# Sheet1.net
KiCad netlist of a schematic drawn in Altium Designer
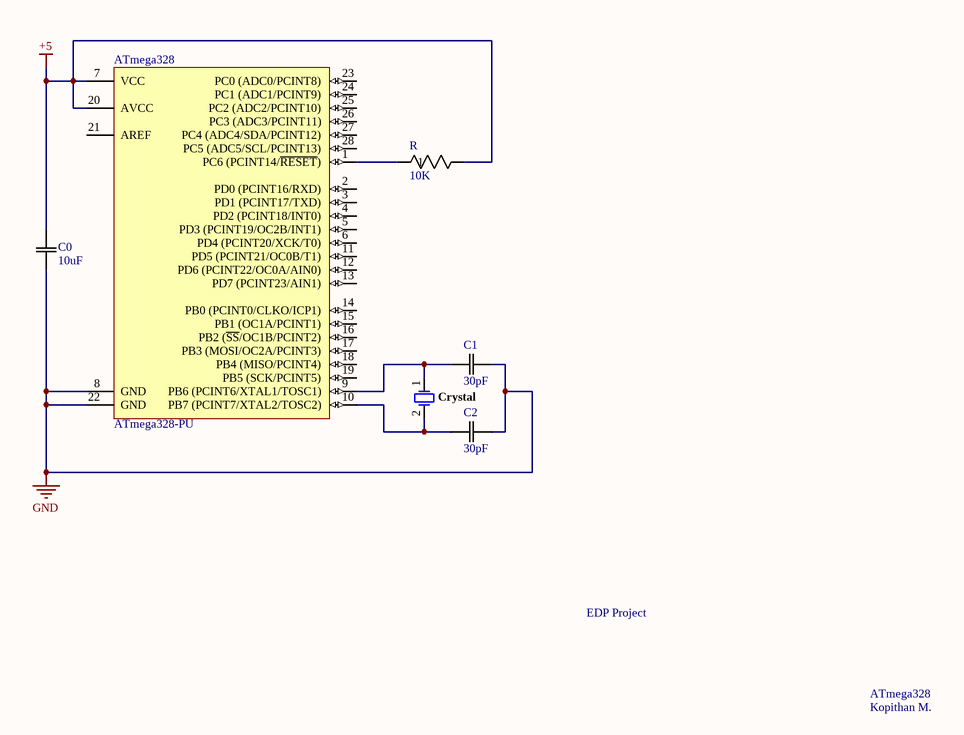
[diagram p0: Sheet1.SchDoc]

(export (version "E")
  (design (tool "Eeschema 10.0.6"))
  (components
    (comp (ref "ATmega328")
      (value "ATmega328-PU")
      (footprint "28P3")
      (libsource (lib "Altium Content Vault") (part "MC-8B-ATM48-IL28"))
    )
    (comp (ref "C0")
      (value "10uF")
      (footprint "CAP_WCAP-PTHR_6P3X8P0_WRE")
      (libsource (lib "870055673001") (part "870055673001"))
    )
    (comp (ref "C1")
      (value "30pF")
      (footprint "CAP_CD15_CND")
      (description "CD15ED300JO3F")
      (libsource (lib "CD15ED300JO3F") (part "CD15ED300JO3F"))
    )
    (comp (ref "C2")
      (value "30pF")
      (footprint "CAP_CD15_CND")
      (description "CD15ED300JO3F")
      (libsource (lib "CD15ED300JO3F") (part "CD15ED300JO3F"))
    )
    (comp (ref "Crystal")
      (value "FOXSLF/160-20")
      (footprint "FOX-FOXSLF160-20")
      (description "Resistance Weld Thru-Hole Crystal, 16 MHz, -20 to 70 degC, 2-Pin THD, RoHS, Bulk")
      (fields (field (name "TOLERANCE") "1%"))
      (libsource (lib "Altium Content Vault") (part "XTAL-1-2-2"))
    )
    (comp (ref "R")
      (value "10K")
      (footprint "RES_TYCO_YR1_TYC")
      (description "30pF")
      (libsource (lib "YR1B10KCC") (part "YR1B10KCC"))
    )
  )
  (nets
    (net (code "1") (name "+5") (class "Default")
      (node (ref "ATmega328") (pin "20") (pinfunction "AVCC_20") (pintype "power_in"))
      (node (ref "ATmega328") (pin "7") (pinfunction "VCC_7") (pintype "power_in"))
      (node (ref "C0") (pin "2") (pinfunction "2_2") (pintype "passive"))
      (node (ref "R") (pin "2") (pinfunction "2_2") (pintype "passive"))
    )
    (net (code "2") (name "GND") (class "Default")
      (node (ref "ATmega328") (pin "22") (pinfunction "GND_22") (pintype "power_in"))
      (node (ref "ATmega328") (pin "8") (pinfunction "GND_8") (pintype "power_in"))
      (node (ref "C0") (pin "1") (pinfunction "1_1") (pintype "passive"))
      (node (ref "C1") (pin "2") (pinfunction "2_2") (pintype "passive"))
      (node (ref "C2") (pin "2") (pinfunction "2_2") (pintype "passive"))
    )
    (net (code "3") (name "Net-(ATmega328-PB6_(PCINT6{slash}XTAL1{slash}TOSC1))") (class "Default")
      (node (ref "ATmega328") (pin "9") (pinfunction "PB6_(PCINT6/XTAL1/TOSC1)_9") (pintype "bidirectional"))
      (node (ref "C1") (pin "1") (pinfunction "1_1") (pintype "passive"))
      (node (ref "Crystal") (pin "1") (pinfunction "1_1") (pintype "passive"))
    )
    (net (code "4") (name "Net-(ATmega328-PB7_(PCINT7{slash}XTAL2{slash}TOSC2))") (class "Default")
      (node (ref "ATmega328") (pin "10") (pinfunction "PB7_(PCINT7/XTAL2/TOSC2)_10") (pintype "bidirectional"))
      (node (ref "C2") (pin "1") (pinfunction "1_1") (pintype "passive"))
      (node (ref "Crystal") (pin "2") (pinfunction "2_2") (pintype "passive"))
    )
    (net (code "5") (name "Net-(ATmega328-PC6_(PCINT14{slash}~{RESET}))") (class "Default")
      (node (ref "ATmega328") (pin "1") (pinfunction "PC6_(PCINT14/~{RESET})_1") (pintype "bidirectional"))
      (node (ref "R") (pin "1") (pinfunction "1_1") (pintype "passive"))
    )
    (net (code "6") (name "unconnected-(ATmega328-AREF-Pad21)") (class "Default")
      (node (ref "ATmega328") (pin "21") (pinfunction "AREF_21") (pintype "power_in"))
    )
    (net (code "7") (name "unconnected-(ATmega328-PB0_(PCINT0{slash}CLKO{slash}ICP1)-Pad14)") (class "Default")
      (node (ref "ATmega328") (pin "14") (pinfunction "PB0_(PCINT0/CLKO/ICP1)_14") (pintype "bidirectional"))
    )
    (net (code "8") (name "unconnected-(ATmega328-PB1_(OC1A{slash}PCINT1)-Pad15)") (class "Default")
      (node (ref "ATmega328") (pin "15") (pinfunction "PB1_(OC1A/PCINT1)_15") (pintype "bidirectional"))
    )
    (net (code "9") (name "unconnected-(ATmega328-PB2_(~{SS}{slash}OC1B{slash}PCINT2)-Pad16)") (class "Default")
      (node (ref "ATmega328") (pin "16") (pinfunction "PB2_(~{SS}/OC1B/PCINT2)_16") (pintype "bidirectional"))
    )
    (net (code "10") (name "unconnected-(ATmega328-PB3_(MOSI{slash}OC2A{slash}PCINT3)-Pad17)") (class "Default")
      (node (ref "ATmega328") (pin "17") (pinfunction "PB3_(MOSI/OC2A/PCINT3)_17") (pintype "bidirectional"))
    )
    (net (code "11") (name "unconnected-(ATmega328-PB4_(MISO{slash}PCINT4)-Pad18)") (class "Default")
      (node (ref "ATmega328") (pin "18") (pinfunction "PB4_(MISO/PCINT4)_18") (pintype "bidirectional"))
    )
    (net (code "12") (name "unconnected-(ATmega328-PB5_(SCK{slash}PCINT5)-Pad19)") (class "Default")
      (node (ref "ATmega328") (pin "19") (pinfunction "PB5_(SCK/PCINT5)_19") (pintype "bidirectional"))
    )
    (net (code "13") (name "unconnected-(ATmega328-PC0_(ADC0{slash}PCINT8)-Pad23)") (class "Default")
      (node (ref "ATmega328") (pin "23") (pinfunction "PC0_(ADC0/PCINT8)_23") (pintype "bidirectional"))
    )
    (net (code "14") (name "unconnected-(ATmega328-PC1_(ADC1{slash}PCINT9)-Pad24)") (class "Default")
      (node (ref "ATmega328") (pin "24") (pinfunction "PC1_(ADC1/PCINT9)_24") (pintype "bidirectional"))
    )
    (net (code "15") (name "unconnected-(ATmega328-PC2_(ADC2{slash}PCINT10)-Pad25)") (class "Default")
      (node (ref "ATmega328") (pin "25") (pinfunction "PC2_(ADC2/PCINT10)_25") (pintype "bidirectional"))
    )
    (net (code "16") (name "unconnected-(ATmega328-PC3_(ADC3{slash}PCINT11)-Pad26)") (class "Default")
      (node (ref "ATmega328") (pin "26") (pinfunction "PC3_(ADC3/PCINT11)_26") (pintype "bidirectional"))
    )
    (net (code "17") (name "unconnected-(ATmega328-PC4_(ADC4{slash}SDA{slash}PCINT12)-Pad27)") (class "Default")
      (node (ref "ATmega328") (pin "27") (pinfunction "PC4_(ADC4/SDA/PCINT12)_27") (pintype "bidirectional"))
    )
    (net (code "18") (name "unconnected-(ATmega328-PC5_(ADC5{slash}SCL{slash}PCINT13)-Pad28)") (class "Default")
      (node (ref "ATmega328") (pin "28") (pinfunction "PC5_(ADC5/SCL/PCINT13)_28") (pintype "bidirectional"))
    )
    (net (code "19") (name "unconnected-(ATmega328-PD0_(PCINT16{slash}RXD)-Pad2)") (class "Default")
      (node (ref "ATmega328") (pin "2") (pinfunction "PD0_(PCINT16/RXD)_2") (pintype "bidirectional"))
    )
    (net (code "20") (name "unconnected-(ATmega328-PD1_(PCINT17{slash}TXD)-Pad3)") (class "Default")
      (node (ref "ATmega328") (pin "3") (pinfunction "PD1_(PCINT17/TXD)_3") (pintype "bidirectional"))
    )
    (net (code "21") (name "unconnected-(ATmega328-PD2_(PCINT18{slash}INT0)-Pad4)") (class "Default")
      (node (ref "ATmega328") (pin "4") (pinfunction "PD2_(PCINT18/INT0)_4") (pintype "bidirectional"))
    )
    (net (code "22") (name "unconnected-(ATmega328-PD3_(PCINT19{slash}OC2B{slash}INT1)-Pad5)") (class "Default")
      (node (ref "ATmega328") (pin "5") (pinfunction "PD3_(PCINT19/OC2B/INT1)_5") (pintype "bidirectional"))
    )
    (net (code "23") (name "unconnected-(ATmega328-PD4_(PCINT20{slash}XCK{slash}T0)-Pad6)") (class "Default")
      (node (ref "ATmega328") (pin "6") (pinfunction "PD4_(PCINT20/XCK/T0)_6") (pintype "bidirectional"))
    )
    (net (code "24") (name "unconnected-(ATmega328-PD5_(PCINT21{slash}OC0B{slash}T1)-Pad11)") (class "Default")
      (node (ref "ATmega328") (pin "11") (pinfunction "PD5_(PCINT21/OC0B/T1)_11") (pintype "bidirectional"))
    )
    (net (code "25") (name "unconnected-(ATmega328-PD6_(PCINT22{slash}OC0A{slash}AIN0)-Pad12)") (class "Default")
      (node (ref "ATmega328") (pin "12") (pinfunction "PD6_(PCINT22/OC0A/AIN0)_12") (pintype "bidirectional"))
    )
    (net (code "26") (name "unconnected-(ATmega328-PD7_(PCINT23{slash}AIN1)-Pad13)") (class "Default")
      (node (ref "ATmega328") (pin "13") (pinfunction "PD7_(PCINT23/AIN1)_13") (pintype "bidirectional"))
    )
  )
)
